# source_B.net
KiCad netlist of a schematic drawn in Altium Designer
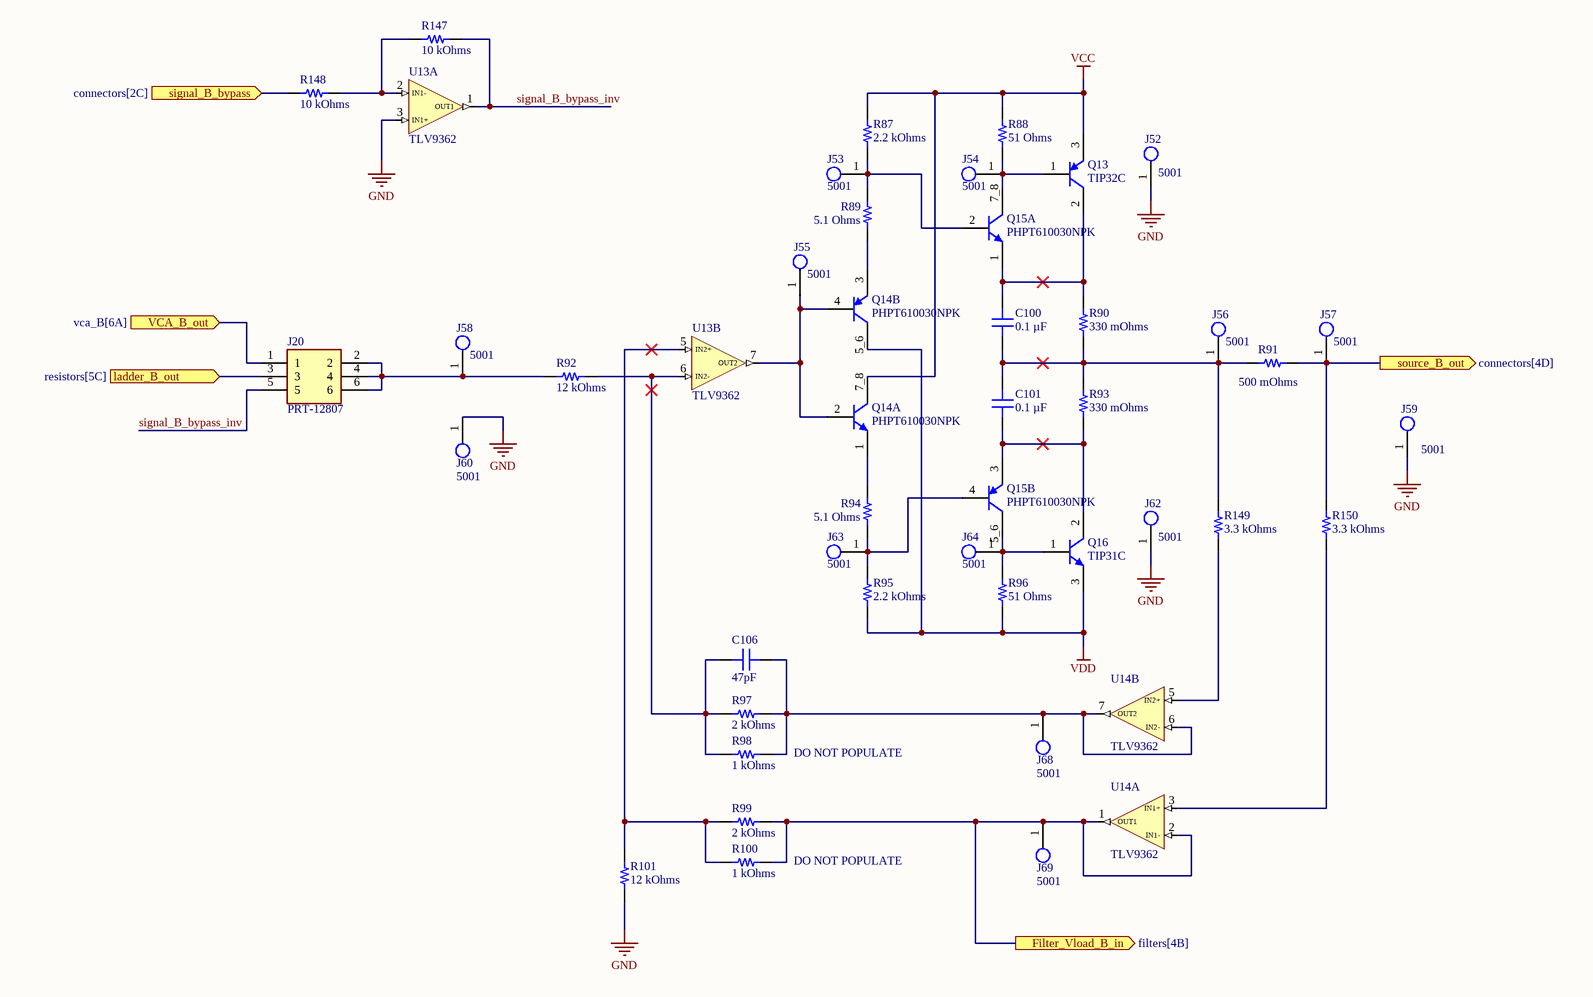
[diagram p0: source_B.SchDoc]

(export (version "E")
  (design (tool "Eeschema 10.0.6"))
  (components
    (comp (ref "C100")
      (value "0.1 µF")
      (footprint "CAP 1206_3216 - 0.8MM")
      (description "CAP CER 0.1UF 50V X7R 1206")
      (fields
        (field (name "PART NUMBER") "885012208087")
        (field (name "CAPACITANCE") "0.1 µF")
        (field (name "MANUFACTURER") "Würth Elektronik")
      )
      (libsource (lib "Celestial Altium Library - altium_library") (part "Capacitor"))
    )
    (comp (ref "C101")
      (value "0.1 µF")
      (footprint "CAP 1206_3216 - 0.8MM")
      (description "CAP CER 0.1UF 50V X7R 1206")
      (fields
        (field (name "PART NUMBER") "885012208087")
        (field (name "CAPACITANCE") "0.1 µF")
        (field (name "MANUFACTURER") "Würth Elektronik")
      )
      (libsource (lib "Celestial Altium Library - altium_library") (part "Capacitor"))
    )
    (comp (ref "C106")
      (value "47pF")
      (footprint "CAP 1206_3216 - 1.8MM")
      (description "CAP CER 47PF 1KV C0G/NP0 1206")
      (fields
        (field (name "PART NUMBER") "1206AA470KAT1A")
        (field (name "CAPACITANCE") "47pF")
        (field (name "MANUFACTURER") "AVX Corporation")
      )
      (libsource (lib "Celestial Altium Library - altium_library") (part "Capacitor"))
    )
    (comp (ref "J20")
      (value "PRT-12807")
      (footprint "HDRV6W82P254_2X3_762X500X884P")
      (description "Connector")
      (fields (field (name "MOUSER PART NUMBER") "474-PRT-12807"))
      (libsource (lib "za_koncar") (part "PRT-12807"))
    )
    (comp (ref "J52")
      (value "5001")
      (footprint "FP-5001-MFG")
      (description "PC TEST POINT MINIATURE BLACK")
      (libsource (lib "za_koncar") (part "CMP-2000-05181-2"))
    )
    (comp (ref "J53")
      (value "5001")
      (footprint "FP-5001-MFG")
      (description "PC TEST POINT MINIATURE BLACK")
      (libsource (lib "za_koncar") (part "CMP-2000-05181-2"))
    )
    (comp (ref "J54")
      (value "5001")
      (footprint "FP-5001-MFG")
      (description "PC TEST POINT MINIATURE BLACK")
      (libsource (lib "za_koncar") (part "CMP-2000-05181-2"))
    )
    (comp (ref "J55")
      (value "5001")
      (footprint "FP-5001-MFG")
      (description "PC TEST POINT MINIATURE BLACK")
      (libsource (lib "za_koncar") (part "CMP-2000-05181-2"))
    )
    (comp (ref "J56")
      (value "5001")
      (footprint "FP-5001-MFG")
      (description "PC TEST POINT MINIATURE BLACK")
      (libsource (lib "za_koncar") (part "CMP-2000-05181-2"))
    )
    (comp (ref "J57")
      (value "5001")
      (footprint "FP-5001-MFG")
      (description "PC TEST POINT MINIATURE BLACK")
      (libsource (lib "za_koncar") (part "CMP-2000-05181-2"))
    )
    (comp (ref "J58")
      (value "5001")
      (footprint "FP-5001-MFG")
      (description "PC TEST POINT MINIATURE BLACK")
      (libsource (lib "za_koncar") (part "CMP-2000-05181-2"))
    )
    (comp (ref "J59")
      (value "5001")
      (footprint "FP-5001-MFG")
      (description "PC TEST POINT MINIATURE BLACK")
      (libsource (lib "za_koncar") (part "CMP-2000-05181-2"))
    )
    (comp (ref "J60")
      (value "5001")
      (footprint "FP-5001-MFG")
      (description "PC TEST POINT MINIATURE BLACK")
      (libsource (lib "za_koncar") (part "CMP-2000-05181-2"))
    )
    (comp (ref "J62")
      (value "5001")
      (footprint "FP-5001-MFG")
      (description "PC TEST POINT MINIATURE BLACK")
      (libsource (lib "za_koncar") (part "CMP-2000-05181-2"))
    )
    (comp (ref "J63")
      (value "5001")
      (footprint "FP-5001-MFG")
      (description "PC TEST POINT MINIATURE BLACK")
      (libsource (lib "za_koncar") (part "CMP-2000-05181-2"))
    )
    (comp (ref "J64")
      (value "5001")
      (footprint "FP-5001-MFG")
      (description "PC TEST POINT MINIATURE BLACK")
      (libsource (lib "za_koncar") (part "CMP-2000-05181-2"))
    )
    (comp (ref "J68")
      (value "5001")
      (footprint "FP-5001-MFG")
      (description "PC TEST POINT MINIATURE BLACK")
      (libsource (lib "za_koncar") (part "CMP-2000-05181-2"))
    )
    (comp (ref "J69")
      (value "5001")
      (footprint "FP-5001-MFG")
      (description "PC TEST POINT MINIATURE BLACK")
      (libsource (lib "za_koncar") (part "CMP-2000-05181-2"))
    )
    (comp (ref "Q13")
      (value "TIP32C")
      (footprint "ONSC-TO-220-3-221A-09")
      (description "Complementary Silicon Plastic Power Transistor, 3-Pin TO-220, Tube")
      (fields (field (name "MANUFACTURER") "On Semiconductor"))
      (libsource (lib "ON Semi General Purpose Transistors") (part "TIP32C"))
    )
    (comp (ref "Q14")
      (value "PHPT610030NPK")
      (footprint "TRANS_BUK9K18-40E,115")
      (libsource (lib "za_koncar") (part "PHPT610030NPK"))
    )
    (comp (ref "Q15")
      (value "PHPT610030NPK")
      (footprint "TRANS_BUK9K18-40E,115")
      (libsource (lib "za_koncar") (part "PHPT610030NPK"))
    )
    (comp (ref "Q16")
      (value "TIP31C")
      (footprint "ONSC-TO-220-3-221A-09")
      (description "Complementary Silicon Plastic Power Transistor, 3-Pin TO-220, Tube")
      (fields (field (name "MANUFACTURER") "On Semiconductor"))
      (libsource (lib "ON Semi General Purpose Transistors") (part "TIP31C"))
    )
    (comp (ref "R87")
      (value "2.2 kOhms")
      (footprint "RES 1206_3216")
      (description "RES SMD 2.2K OHM 5% 1/4W 1206")
      (fields
        (field (name "PART NUMBER") "ERJ-8GEYJ222V")
        (field (name "MANUFACTURER") "Panasonic Electronic Components")
      )
      (libsource (lib "Celestial Altium Library - altium_library") (part "Resistor"))
    )
    (comp (ref "R88")
      (value "51 Ohms")
      (footprint "RES 1206_3216")
      (description "RES SMD 51 OHM 5% 1/4W 1206")
      (fields
        (field (name "PART NUMBER") "ERJ-8GEYJ510V")
        (field (name "MANUFACTURER") "Panasonic Electronic Components")
      )
      (libsource (lib "Celestial Altium Library - altium_library") (part "Resistor"))
    )
    (comp (ref "R89")
      (value "5.1 Ohms")
      (footprint "RES 1206_3216")
      (description "RES SMD 5.1 OHM 5% 1/4W 1206")
      (fields
        (field (name "PART NUMBER") "ERJ-8GEYJ5R1V")
        (field (name "MANUFACTURER") "Panasonic Electronic Components")
      )
      (libsource (lib "Celestial Altium Library - altium_library") (part "Resistor"))
    )
    (comp (ref "R90")
      (value "330 mOhms")
      (footprint "STACKPOLE CSR2512")
      (description "RES 0.33 OHM 1% 2W 2512")
      (fields
        (field (name "PART NUMBER") "CSRN2512FKR330")
        (field (name "MANUFACTURER") "Stackpole Electronics Inc")
      )
      (libsource (lib "Celestial Altium Library - altium_library") (part "Resistor"))
    )
    (comp (ref "R91")
      (value "500 mOhms")
      (footprint "STACKPOLE CSR2512")
      (description "RES 0.5 OHM 1% 2W 2512")
      (fields
        (field (name "PART NUMBER") "CSRN2512FKR500")
        (field (name "MANUFACTURER") "Stackpole Electronics Inc")
      )
      (libsource (lib "Celestial Altium Library - altium_library") (part "Resistor"))
    )
    (comp (ref "R92")
      (value "12 kOhms")
      (footprint "RES 1206_3216")
      (description "RES SMD 12K OHM 0.1% 1/4W 1206")
      (fields
        (field (name "PART NUMBER") "ERA-8AEB123V")
        (field (name "MANUFACTURER") "Panasonic Electronic Components")
      )
      (libsource (lib "Celestial Altium Library - altium_library") (part "Resistor"))
    )
    (comp (ref "R93")
      (value "330 mOhms")
      (footprint "STACKPOLE CSR2512")
      (description "RES 0.33 OHM 1% 2W 2512")
      (fields
        (field (name "PART NUMBER") "CSRN2512FKR330")
        (field (name "MANUFACTURER") "Stackpole Electronics Inc")
      )
      (libsource (lib "Celestial Altium Library - altium_library") (part "Resistor"))
    )
    (comp (ref "R94")
      (value "5.1 Ohms")
      (footprint "RES 1206_3216")
      (description "RES SMD 5.1 OHM 5% 1/4W 1206")
      (fields
        (field (name "PART NUMBER") "ERJ-8GEYJ5R1V")
        (field (name "MANUFACTURER") "Panasonic Electronic Components")
      )
      (libsource (lib "Celestial Altium Library - altium_library") (part "Resistor"))
    )
    (comp (ref "R95")
      (value "2.2 kOhms")
      (footprint "RES 1206_3216")
      (description "RES SMD 2.2K OHM 5% 1/4W 1206")
      (fields
        (field (name "PART NUMBER") "ERJ-8GEYJ222V")
        (field (name "MANUFACTURER") "Panasonic Electronic Components")
      )
      (libsource (lib "Celestial Altium Library - altium_library") (part "Resistor"))
    )
    (comp (ref "R96")
      (value "51 Ohms")
      (footprint "RES 1206_3216")
      (description "RES SMD 51 OHM 5% 1/4W 1206")
      (fields
        (field (name "PART NUMBER") "ERJ-8GEYJ510V")
        (field (name "MANUFACTURER") "Panasonic Electronic Components")
      )
      (libsource (lib "Celestial Altium Library - altium_library") (part "Resistor"))
    )
    (comp (ref "R97")
      (value "2 kOhms")
      (footprint "RES 1206_3216")
      (description "RES SMD 2K OHM 0.1% 1/4W 1206")
      (fields
        (field (name "PART NUMBER") "ERA-8AEB202V")
        (field (name "MANUFACTURER") "Panasonic Electronic Components")
      )
      (libsource (lib "Celestial Altium Library - altium_library") (part "Resistor"))
    )
    (comp (ref "R98")
      (value "1 kOhms")
      (footprint "RES 1206_3216")
      (description "RES SMD 1K OHM 0.1% 1/4W 1206")
      (fields
        (field (name "PART NUMBER") "ERA-8AEB102V")
        (field (name "MANUFACTURER") "Panasonic Electronic Components")
      )
      (libsource (lib "Celestial Altium Library - altium_library") (part "Resistor"))
    )
    (comp (ref "R99")
      (value "2 kOhms")
      (footprint "RES 1206_3216")
      (description "RES SMD 2K OHM 0.1% 1/4W 1206")
      (fields
        (field (name "PART NUMBER") "ERA-8AEB202V")
        (field (name "MANUFACTURER") "Panasonic Electronic Components")
      )
      (libsource (lib "Celestial Altium Library - altium_library") (part "Resistor"))
    )
    (comp (ref "R100")
      (value "1 kOhms")
      (footprint "RES 1206_3216")
      (description "RES SMD 1K OHM 0.1% 1/4W 1206")
      (fields
        (field (name "PART NUMBER") "ERA-8AEB102V")
        (field (name "MANUFACTURER") "Panasonic Electronic Components")
      )
      (libsource (lib "Celestial Altium Library - altium_library") (part "Resistor"))
    )
    (comp (ref "R101")
      (value "12 kOhms")
      (footprint "RES 1206_3216")
      (description "RES SMD 12K OHM 0.1% 1/4W 1206")
      (fields
        (field (name "PART NUMBER") "ERA-8AEB123V")
        (field (name "MANUFACTURER") "Panasonic Electronic Components")
      )
      (libsource (lib "Celestial Altium Library - altium_library") (part "Resistor"))
    )
    (comp (ref "R147")
      (value "10 kOhms")
      (footprint "YAGEO RES 1206_3216")
      (description "RES SMD 10K OHM 1% 1/4W 1206")
      (fields (field (name "PART NUMBER") "RT1206FRE0710KL") (field (name "MANUFACTURER") "Yageo"))
      (libsource (lib "Celestial Altium Library - altium_library") (part "Resistor"))
    )
    (comp (ref "R148")
      (value "10 kOhms")
      (footprint "YAGEO RES 1206_3216")
      (description "RES SMD 10K OHM 1% 1/4W 1206")
      (fields (field (name "PART NUMBER") "RT1206FRE0710KL") (field (name "MANUFACTURER") "Yageo"))
      (libsource (lib "Celestial Altium Library - altium_library") (part "Resistor"))
    )
    (comp (ref "R149")
      (value "3.3 kOhms")
      (footprint "YAGEO RES 1206_3216")
      (description "RES SMD 3.3K OHM 1% 1/4W 1206")
      (fields (field (name "PART NUMBER") "RT1206FRE073K3L") (field (name "MANUFACTURER") "Yageo"))
      (libsource (lib "Celestial Altium Library - altium_library") (part "Resistor"))
    )
    (comp (ref "R150")
      (value "3.3 kOhms")
      (footprint "YAGEO RES 1206_3216")
      (description "RES SMD 3.3K OHM 1% 1/4W 1206")
      (fields (field (name "PART NUMBER") "RT1206FRE073K3L") (field (name "MANUFACTURER") "Yageo"))
      (libsource (lib "Celestial Altium Library - altium_library") (part "Resistor"))
    )
    (comp (ref "U13")
      (value "TLV9362")
      (footprint "za_koncar:SOIC8-127P600X175-8N")
      (description "TLV936x 10-MHz, 40-V, RRO, Operational Amplifie")
      (libsource (lib "za_koncar") (part "TLV9362"))
    )
    (comp (ref "U14")
      (value "TLV9362")
      (footprint "za_koncar:SOIC8-127P600X175-8N")
      (description "TLV936x 10-MHz, 40-V, RRO, Operational Amplifie")
      (libsource (lib "za_koncar") (part "TLV9362"))
    )
  )
  (nets
    (net (code "1") (name "/Filter_Vload_B_in") (class "Default")
      (node (ref "J69") (pin "1") (pinfunction "1_1") (pintype "passive"))
      (node (ref "R100") (pin "2") (pinfunction "2_2") (pintype "passive"))
      (node (ref "R99") (pin "2") (pinfunction "2_2") (pintype "passive"))
      (node (ref "U14") (pin "1") (pinfunction "OUT1_1") (pintype "output"))
      (node (ref "U14") (pin "2") (pinfunction "IN1-_2") (pintype "input"))
    )
    (net (code "2") (name "/VCA_B_out") (class "Default")
      (node (ref "J20") (pin "1") (pinfunction "1_1") (pintype "passive"))
    )
    (net (code "3") (name "/ladder_B_out") (class "Default")
      (node (ref "J20") (pin "3") (pinfunction "3_3") (pintype "passive"))
    )
    (net (code "4") (name "/signal_B_bypass") (class "Default")
      (node (ref "R148") (pin "2") (pinfunction "2_2") (pintype "passive"))
    )
    (net (code "5") (name "/signal_B_bypass_inv") (class "Default")
      (node (ref "J20") (pin "5") (pinfunction "5_5") (pintype "passive"))
      (node (ref "R147") (pin "2") (pinfunction "2_2") (pintype "passive"))
      (node (ref "U13") (pin "1") (pinfunction "OUT1_1") (pintype "output"))
    )
    (net (code "6") (name "/source_B_out") (class "Default")
      (node (ref "J57") (pin "1") (pinfunction "1_1") (pintype "passive"))
      (node (ref "R150") (pin "1") (pinfunction "1_1") (pintype "passive"))
      (node (ref "R91") (pin "1") (pinfunction "1_1") (pintype "passive"))
    )
    (net (code "7") (name "GND") (class "Default")
      (node (ref "J52") (pin "1") (pinfunction "1_1") (pintype "passive"))
      (node (ref "J59") (pin "1") (pinfunction "1_1") (pintype "passive"))
      (node (ref "J60") (pin "1") (pinfunction "1_1") (pintype "passive"))
      (node (ref "J62") (pin "1") (pinfunction "1_1") (pintype "passive"))
      (node (ref "R101") (pin "1") (pinfunction "1_1") (pintype "passive"))
      (node (ref "U13") (pin "3") (pinfunction "IN1+_3") (pintype "input"))
    )
    (net (code "8") (name "Net-(C100-Pad1)") (class "Default")
      (node (ref "C100") (pin "1") (pinfunction "1_1") (pintype "passive"))
      (node (ref "C101") (pin "2") (pinfunction "2_2") (pintype "passive"))
      (node (ref "J56") (pin "1") (pinfunction "1_1") (pintype "passive"))
      (node (ref "R149") (pin "1") (pinfunction "1_1") (pintype "passive"))
      (node (ref "R90") (pin "1") (pinfunction "1_1") (pintype "passive"))
      (node (ref "R91") (pin "2") (pinfunction "2_2") (pintype "passive"))
      (node (ref "R93") (pin "2") (pinfunction "2_2") (pintype "passive"))
    )
    (net (code "9") (name "Net-(J20-Pad2)") (class "Default")
      (node (ref "J20") (pin "2") (pinfunction "2_2") (pintype "passive"))
      (node (ref "J20") (pin "4") (pinfunction "4_4") (pintype "passive"))
      (node (ref "J20") (pin "6") (pinfunction "6_6") (pintype "passive"))
      (node (ref "J58") (pin "1") (pinfunction "1_1") (pintype "passive"))
      (node (ref "R92") (pin "2") (pinfunction "2_2") (pintype "passive"))
    )
    (net (code "10") (name "Net-(Q13-B)") (class "Default")
      (node (ref "J54") (pin "1") (pinfunction "1_1") (pintype "passive"))
      (node (ref "Q13") (pin "1") (pinfunction "B_1") (pintype "passive"))
      (node (ref "Q15") (pin "7_8") (pinfunction "C1_7_8") (pintype "passive"))
      (node (ref "R88") (pin "1") (pinfunction "1_1") (pintype "passive"))
    )
    (net (code "11") (name "Net-(Q13-C)") (class "Default")
      (node (ref "C100") (pin "2") (pinfunction "2_2") (pintype "passive"))
      (node (ref "Q13") (pin "2") (pinfunction "C_2") (pintype "passive"))
      (node (ref "Q15") (pin "1") (pinfunction "E1_1") (pintype "passive"))
      (node (ref "R90") (pin "2") (pinfunction "2_2") (pintype "passive"))
    )
    (net (code "12") (name "Net-(Q14A-B1)") (class "Default")
      (node (ref "J55") (pin "1") (pinfunction "1_1") (pintype "passive"))
      (node (ref "Q14") (pin "2") (pinfunction "B1_2") (pintype "passive"))
      (node (ref "Q14") (pin "4") (pinfunction "B2_4") (pintype "passive"))
      (node (ref "U13") (pin "7") (pinfunction "OUT2_7") (pintype "output"))
    )
    (net (code "13") (name "Net-(Q14A-E1)") (class "Default")
      (node (ref "Q14") (pin "1") (pinfunction "E1_1") (pintype "passive"))
      (node (ref "R94") (pin "2") (pinfunction "2_2") (pintype "passive"))
    )
    (net (code "14") (name "Net-(Q14B-E2)") (class "Default")
      (node (ref "Q14") (pin "3") (pinfunction "E2_3") (pintype "passive"))
      (node (ref "R89") (pin "1") (pinfunction "1_1") (pintype "passive"))
    )
    (net (code "15") (name "Net-(Q15A-B1)") (class "Default")
      (node (ref "J53") (pin "1") (pinfunction "1_1") (pintype "passive"))
      (node (ref "Q15") (pin "2") (pinfunction "B1_2") (pintype "passive"))
      (node (ref "R87") (pin "1") (pinfunction "1_1") (pintype "passive"))
      (node (ref "R89") (pin "2") (pinfunction "2_2") (pintype "passive"))
    )
    (net (code "16") (name "Net-(Q15B-B2)") (class "Default")
      (node (ref "J63") (pin "1") (pinfunction "1_1") (pintype "passive"))
      (node (ref "Q15") (pin "4") (pinfunction "B2_4") (pintype "passive"))
      (node (ref "R94") (pin "1") (pinfunction "1_1") (pintype "passive"))
      (node (ref "R95") (pin "2") (pinfunction "2_2") (pintype "passive"))
    )
    (net (code "17") (name "Net-(Q15B-C2)") (class "Default")
      (node (ref "J64") (pin "1") (pinfunction "1_1") (pintype "passive"))
      (node (ref "Q15") (pin "5_6") (pinfunction "C2_5_6") (pintype "passive"))
      (node (ref "Q16") (pin "1") (pinfunction "B_1") (pintype "passive"))
      (node (ref "R96") (pin "2") (pinfunction "2_2") (pintype "passive"))
    )
    (net (code "18") (name "Net-(Q15B-E2)") (class "Default")
      (node (ref "C101") (pin "1") (pinfunction "1_1") (pintype "passive"))
      (node (ref "Q15") (pin "3") (pinfunction "E2_3") (pintype "passive"))
      (node (ref "Q16") (pin "2") (pinfunction "C_2") (pintype "passive"))
      (node (ref "R93") (pin "1") (pinfunction "1_1") (pintype "passive"))
    )
    (net (code "19") (name "Net-(U13A-IN1-)") (class "Default")
      (node (ref "R147") (pin "1") (pinfunction "1_1") (pintype "passive"))
      (node (ref "R148") (pin "1") (pinfunction "1_1") (pintype "passive"))
      (node (ref "U13") (pin "2") (pinfunction "IN1-_2") (pintype "input"))
    )
    (net (code "20") (name "Net-(U13B-IN2+)") (class "Default")
      (node (ref "R100") (pin "1") (pinfunction "1_1") (pintype "passive"))
      (node (ref "R101") (pin "2") (pinfunction "2_2") (pintype "passive"))
      (node (ref "R99") (pin "1") (pinfunction "1_1") (pintype "passive"))
      (node (ref "U13") (pin "5") (pinfunction "IN2+_5") (pintype "input"))
    )
    (net (code "21") (name "Net-(U13B-IN2-)") (class "Default")
      (node (ref "C106") (pin "1") (pinfunction "1_1") (pintype "passive"))
      (node (ref "R92") (pin "1") (pinfunction "1_1") (pintype "passive"))
      (node (ref "R97") (pin "1") (pinfunction "1_1") (pintype "passive"))
      (node (ref "R98") (pin "1") (pinfunction "1_1") (pintype "passive"))
      (node (ref "U13") (pin "6") (pinfunction "IN2-_6") (pintype "input"))
    )
    (net (code "22") (name "Net-(U14A-IN1+)") (class "Default")
      (node (ref "R150") (pin "2") (pinfunction "2_2") (pintype "passive"))
      (node (ref "U14") (pin "3") (pinfunction "IN1+_3") (pintype "input"))
    )
    (net (code "23") (name "Net-(U14B-IN2+)") (class "Default")
      (node (ref "R149") (pin "2") (pinfunction "2_2") (pintype "passive"))
      (node (ref "U14") (pin "5") (pinfunction "IN2+_5") (pintype "input"))
    )
    (net (code "24") (name "Net-(U14B-IN2-)") (class "Default")
      (node (ref "C106") (pin "2") (pinfunction "2_2") (pintype "passive"))
      (node (ref "J68") (pin "1") (pinfunction "1_1") (pintype "passive"))
      (node (ref "R97") (pin "2") (pinfunction "2_2") (pintype "passive"))
      (node (ref "R98") (pin "2") (pinfunction "2_2") (pintype "passive"))
      (node (ref "U14") (pin "6") (pinfunction "IN2-_6") (pintype "input"))
      (node (ref "U14") (pin "7") (pinfunction "OUT2_7") (pintype "output"))
    )
    (net (code "25") (name "VCC") (class "Default")
      (node (ref "Q13") (pin "3") (pinfunction "E_3") (pintype "passive"))
      (node (ref "Q14") (pin "7_8") (pinfunction "C1_7_8") (pintype "passive"))
      (node (ref "R87") (pin "2") (pinfunction "2_2") (pintype "passive"))
      (node (ref "R88") (pin "2") (pinfunction "2_2") (pintype "passive"))
    )
    (net (code "26") (name "VDD") (class "Default")
      (node (ref "Q14") (pin "5_6") (pinfunction "C2_5_6") (pintype "passive"))
      (node (ref "Q16") (pin "3") (pinfunction "E_3") (pintype "passive"))
      (node (ref "R95") (pin "1") (pinfunction "1_1") (pintype "passive"))
      (node (ref "R96") (pin "1") (pinfunction "1_1") (pintype "passive"))
    )
  )
)
